# Piggyback-Board.net
KiCad netlist of a schematic drawn in EAGLE
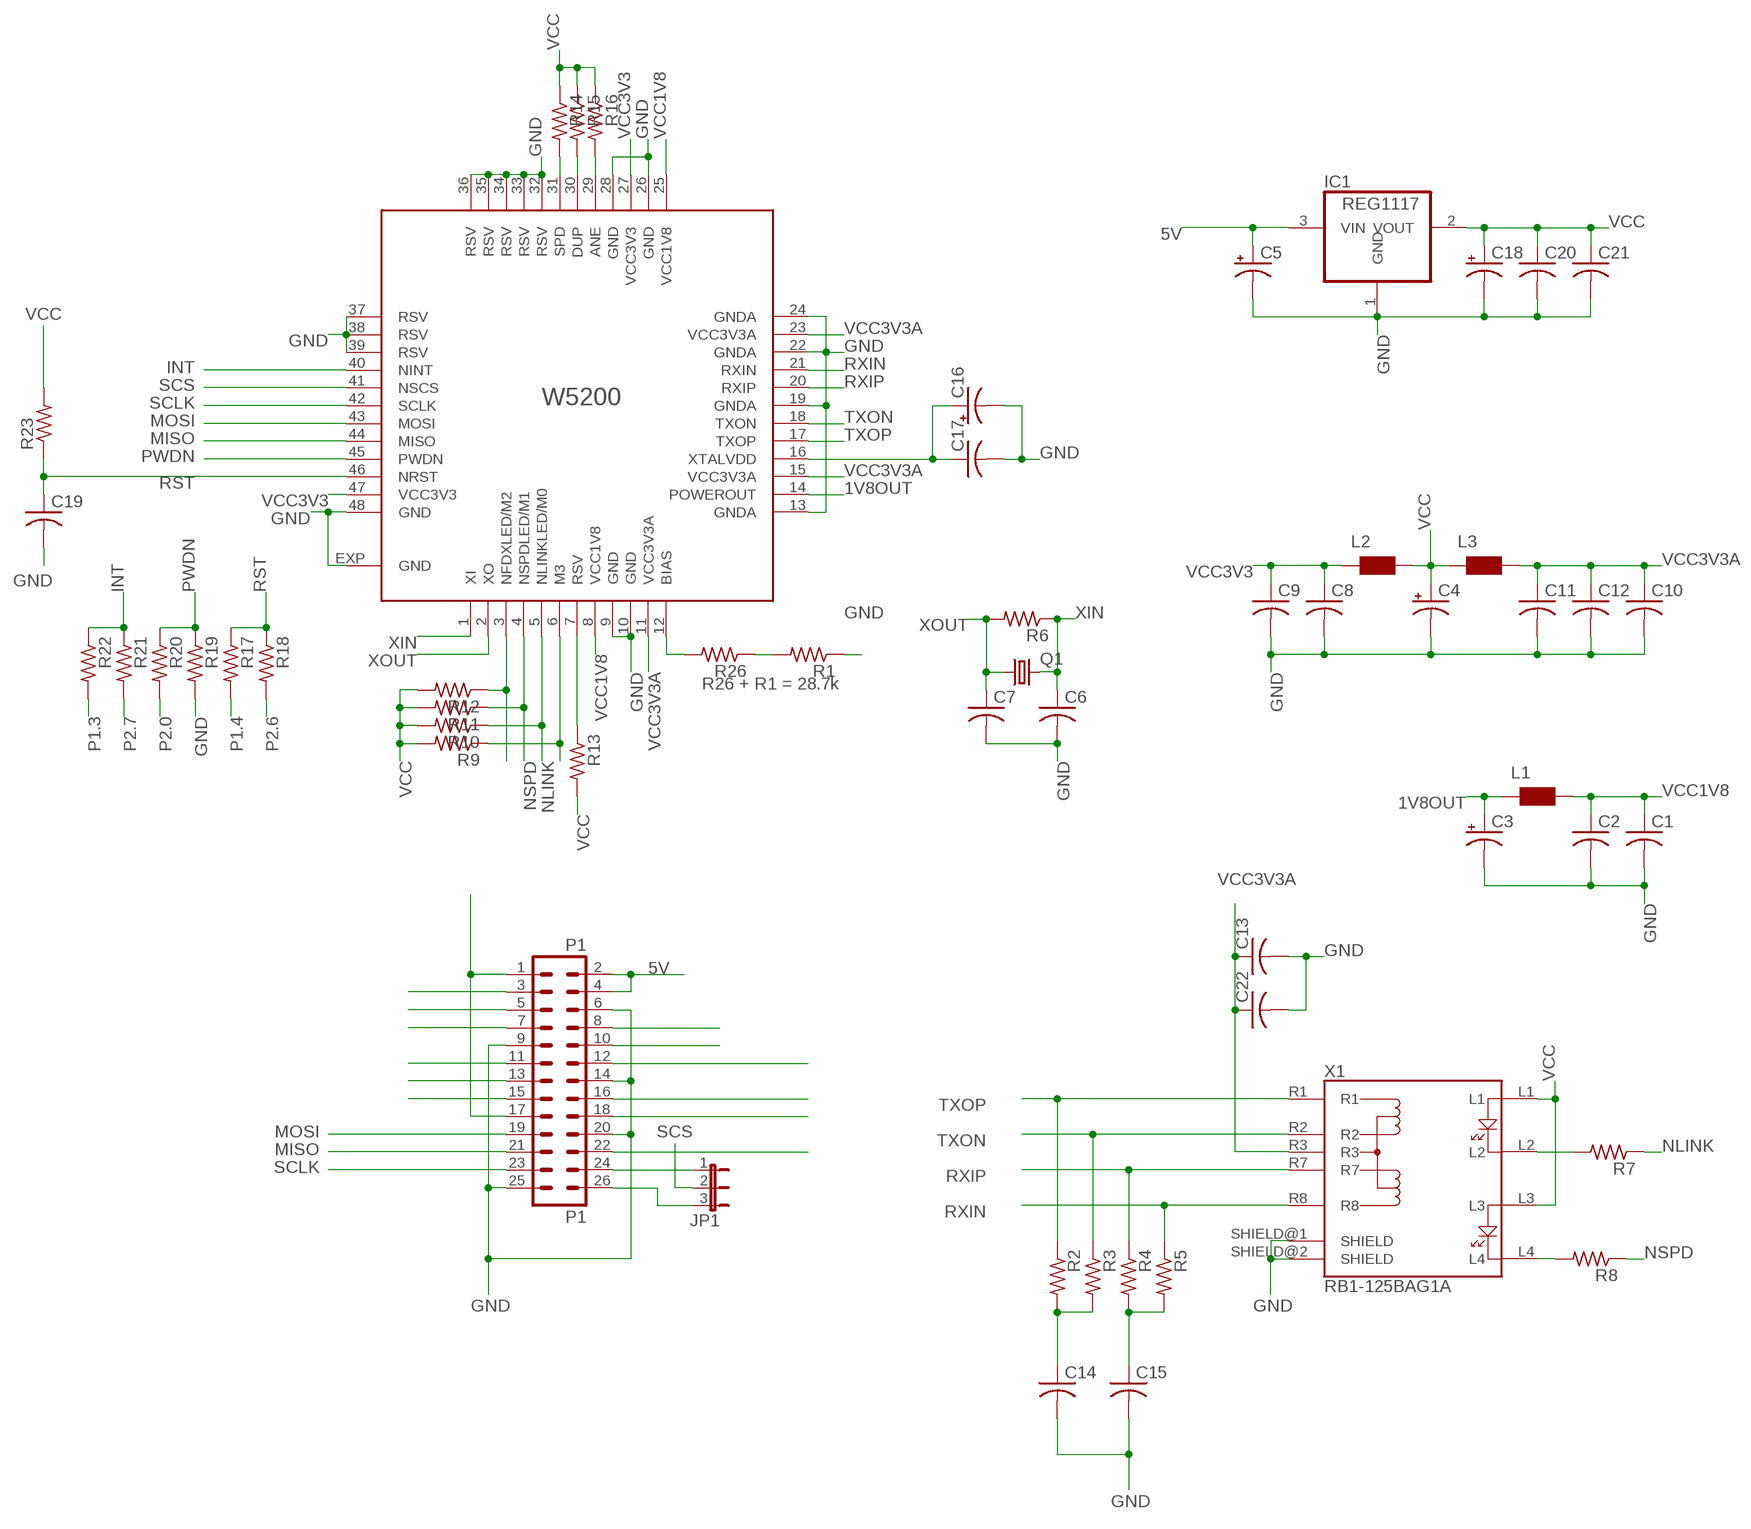
[diagram p0: schematic, sheet 1]

(export (version "E")
  (design (tool "Eeschema 10.0.6"))
  (components
    (comp (ref "C1")
      (value "C-USC0603")
      (footprint "eagle-import:C0603")
      (libsource (lib "eagle-import") (part "C-USC0603"))
    )
    (comp (ref "C2")
      (value "C-USC0603")
      (footprint "eagle-import:C0603")
      (libsource (lib "eagle-import") (part "C-USC0603"))
    )
    (comp (ref "C3")
      (value "CPOL-USA/3216-18R")
      (footprint "eagle-import:A_3216-18R")
      (libsource (lib "eagle-import") (part "CPOL-USA/3216-18R"))
    )
    (comp (ref "C4")
      (value "CPOL-USA/3216-18R")
      (footprint "eagle-import:A_3216-18R")
      (libsource (lib "eagle-import") (part "CPOL-USA/3216-18R"))
    )
    (comp (ref "C5")
      (value "CPOL-USB/3528-21R")
      (footprint "eagle-import:B_3528-21R")
      (libsource (lib "eagle-import") (part "CPOL-USB/3528-21R"))
    )
    (comp (ref "C6")
      (value "C-USC0603")
      (footprint "eagle-import:C0603")
      (libsource (lib "eagle-import") (part "C-USC0603"))
    )
    (comp (ref "C7")
      (value "C-USC0603")
      (footprint "eagle-import:C0603")
      (libsource (lib "eagle-import") (part "C-USC0603"))
    )
    (comp (ref "C8")
      (value "C-USC0603")
      (footprint "eagle-import:C0603")
      (libsource (lib "eagle-import") (part "C-USC0603"))
    )
    (comp (ref "C9")
      (value "C-USC0603")
      (footprint "eagle-import:C0603")
      (libsource (lib "eagle-import") (part "C-USC0603"))
    )
    (comp (ref "C10")
      (value "C-USC0603")
      (footprint "eagle-import:C0603")
      (libsource (lib "eagle-import") (part "C-USC0603"))
    )
    (comp (ref "C11")
      (value "C-USC0603")
      (footprint "eagle-import:C0603")
      (libsource (lib "eagle-import") (part "C-USC0603"))
    )
    (comp (ref "C12")
      (value "C-USC0603")
      (footprint "eagle-import:C0603")
      (libsource (lib "eagle-import") (part "C-USC0603"))
    )
    (comp (ref "C13")
      (value "C-USC0603")
      (footprint "eagle-import:C0603")
      (libsource (lib "eagle-import") (part "C-USC0603"))
    )
    (comp (ref "C14")
      (value "C-USC0603")
      (footprint "eagle-import:C0603")
      (libsource (lib "eagle-import") (part "C-USC0603"))
    )
    (comp (ref "C15")
      (value "C-USC0603")
      (footprint "eagle-import:C0603")
      (libsource (lib "eagle-import") (part "C-USC0603"))
    )
    (comp (ref "C16")
      (value "CPOL-USA/3216-18R")
      (footprint "eagle-import:A_3216-18R")
      (libsource (lib "eagle-import") (part "CPOL-USA/3216-18R"))
    )
    (comp (ref "C17")
      (value "C-USC0603")
      (footprint "eagle-import:C0603")
      (libsource (lib "eagle-import") (part "C-USC0603"))
    )
    (comp (ref "C18")
      (value "CPOL-USB/3528-21R")
      (footprint "eagle-import:B_3528-21R")
      (libsource (lib "eagle-import") (part "CPOL-USB/3528-21R"))
    )
    (comp (ref "C19")
      (value "C-USC0603")
      (footprint "eagle-import:C0603")
      (libsource (lib "eagle-import") (part "C-USC0603"))
    )
    (comp (ref "C20")
      (value "C-USC0603")
      (footprint "eagle-import:C0603")
      (libsource (lib "eagle-import") (part "C-USC0603"))
    )
    (comp (ref "C21")
      (value "C-USC0603")
      (footprint "eagle-import:C0603")
      (libsource (lib "eagle-import") (part "C-USC0603"))
    )
    (comp (ref "C22")
      (value "C-USC0603")
      (footprint "eagle-import:C0603")
      (libsource (lib "eagle-import") (part "C-USC0603"))
    )
    (comp (ref "IC1")
      (value "REG1117")
      (footprint "eagle-import:SOT223")
      (libsource (lib "eagle-import") (part "REG1117"))
    )
    (comp (ref "JP1")
      (value "JP2E")
      (footprint "eagle-import:JP2")
      (libsource (lib "eagle-import") (part "JP2E"))
    )
    (comp (ref "L1")
      (value "WE-CBF_0603")
      (footprint "eagle-import:0603")
      (libsource (lib "eagle-import") (part "WE-CBF_0603"))
    )
    (comp (ref "L2")
      (value "WE-CBF_0603")
      (footprint "eagle-import:0603")
      (libsource (lib "eagle-import") (part "WE-CBF_0603"))
    )
    (comp (ref "L3")
      (value "WE-CBF_0603")
      (footprint "eagle-import:0603")
      (libsource (lib "eagle-import") (part "WE-CBF_0603"))
    )
    (comp (ref "P1")
      (value "P1")
      (footprint "eagle-import:MA13-2")
      (libsource (lib "eagle-import") (part "MA13-2"))
    )
    (comp (ref "Q1")
      (value "CRYSTALSM49")
      (footprint "eagle-import:SM49")
      (libsource (lib "eagle-import") (part "CRYSTALSM49"))
    )
    (comp (ref "R1")
      (value "R-US_R0603")
      (footprint "eagle-import:R0603")
      (libsource (lib "eagle-import") (part "R-US_R0603"))
    )
    (comp (ref "R2")
      (value "R-US_R0603")
      (footprint "eagle-import:R0603")
      (libsource (lib "eagle-import") (part "R-US_R0603"))
    )
    (comp (ref "R3")
      (value "R-US_R0603")
      (footprint "eagle-import:R0603")
      (libsource (lib "eagle-import") (part "R-US_R0603"))
    )
    (comp (ref "R4")
      (value "R-US_R0603")
      (footprint "eagle-import:R0603")
      (libsource (lib "eagle-import") (part "R-US_R0603"))
    )
    (comp (ref "R5")
      (value "R-US_R0603")
      (footprint "eagle-import:R0603")
      (libsource (lib "eagle-import") (part "R-US_R0603"))
    )
    (comp (ref "R6")
      (value "R-US_R0603")
      (footprint "eagle-import:R0603")
      (libsource (lib "eagle-import") (part "R-US_R0603"))
    )
    (comp (ref "R7")
      (value "R-US_R0603")
      (footprint "eagle-import:R0603")
      (libsource (lib "eagle-import") (part "R-US_R0603"))
    )
    (comp (ref "R8")
      (value "R-US_R0603")
      (footprint "eagle-import:R0603")
      (libsource (lib "eagle-import") (part "R-US_R0603"))
    )
    (comp (ref "R9")
      (value "R-US_R0603")
      (footprint "eagle-import:R0603")
      (libsource (lib "eagle-import") (part "R-US_R0603"))
    )
    (comp (ref "R10")
      (value "R-US_R0603")
      (footprint "eagle-import:R0603")
      (libsource (lib "eagle-import") (part "R-US_R0603"))
    )
    (comp (ref "R11")
      (value "R-US_R0603")
      (footprint "eagle-import:R0603")
      (libsource (lib "eagle-import") (part "R-US_R0603"))
    )
    (comp (ref "R12")
      (value "R-US_R0603")
      (footprint "eagle-import:R0603")
      (libsource (lib "eagle-import") (part "R-US_R0603"))
    )
    (comp (ref "R13")
      (value "R-US_R0603")
      (footprint "eagle-import:R0603")
      (libsource (lib "eagle-import") (part "R-US_R0603"))
    )
    (comp (ref "R14")
      (value "R-US_R0603")
      (footprint "eagle-import:R0603")
      (libsource (lib "eagle-import") (part "R-US_R0603"))
    )
    (comp (ref "R15")
      (value "R-US_R0603")
      (footprint "eagle-import:R0603")
      (libsource (lib "eagle-import") (part "R-US_R0603"))
    )
    (comp (ref "R16")
      (value "R-US_R0603")
      (footprint "eagle-import:R0603")
      (libsource (lib "eagle-import") (part "R-US_R0603"))
    )
    (comp (ref "R17")
      (value "R-US_R0603")
      (footprint "eagle-import:R0603")
      (libsource (lib "eagle-import") (part "R-US_R0603"))
    )
    (comp (ref "R18")
      (value "R-US_R0603")
      (footprint "eagle-import:R0603")
      (libsource (lib "eagle-import") (part "R-US_R0603"))
    )
    (comp (ref "R19")
      (value "R-US_R0603")
      (footprint "eagle-import:R0603")
      (libsource (lib "eagle-import") (part "R-US_R0603"))
    )
    (comp (ref "R20")
      (value "R-US_R0603")
      (footprint "eagle-import:R0603")
      (libsource (lib "eagle-import") (part "R-US_R0603"))
    )
    (comp (ref "R21")
      (value "R-US_R0603")
      (footprint "eagle-import:R0603")
      (libsource (lib "eagle-import") (part "R-US_R0603"))
    )
    (comp (ref "R22")
      (value "R-US_R0603")
      (footprint "eagle-import:R0603")
      (libsource (lib "eagle-import") (part "R-US_R0603"))
    )
    (comp (ref "R23")
      (value "R-US_R0603")
      (footprint "eagle-import:R0603")
      (libsource (lib "eagle-import") (part "R-US_R0603"))
    )
    (comp (ref "R26")
      (value "R-US_R0603")
      (footprint "eagle-import:R0603")
      (libsource (lib "eagle-import") (part "R-US_R0603"))
    )
    (comp (ref "W5200")
      (value "W5200")
      (footprint "eagle-import:QFN48")
      (libsource (lib "eagle-import") (part "W5200"))
    )
    (comp (ref "X1")
      (value "RB1-125BAG1A")
      (footprint "eagle-import:RB1-125BAG1A")
      (libsource (lib "eagle-import") (part "RB1-125BAG1A"))
    )
  )
  (nets
    (net (code "1") (name "/1V8OUT") (class "Default")
      (node (ref "C3") (pin "+") (pinfunction "+_+") (pintype "passive"))
      (node (ref "L1") (pin "1") (pinfunction "1_1") (pintype "passive"))
      (node (ref "W5200") (pin "14") (pinfunction "POWEROUT_14") (pintype "bidirectional"))
    )
    (net (code "2") (name "/5V") (class "Default")
      (node (ref "C5") (pin "+") (pinfunction "+_+") (pintype "passive"))
      (node (ref "IC1") (pin "3") (pinfunction "VIN_3") (pintype "input"))
      (node (ref "P1") (pin "2") (pinfunction "2_2") (pintype "passive"))
      (node (ref "P1") (pin "4") (pinfunction "4_4") (pintype "passive"))
    )
    (net (code "3") (name "/GND") (class "Default")
      (node (ref "C1") (pin "2") (pinfunction "2_2") (pintype "passive"))
      (node (ref "C10") (pin "2") (pinfunction "2_2") (pintype "passive"))
      (node (ref "C11") (pin "2") (pinfunction "2_2") (pintype "passive"))
      (node (ref "C12") (pin "2") (pinfunction "2_2") (pintype "passive"))
      (node (ref "C13") (pin "2") (pinfunction "2_2") (pintype "passive"))
      (node (ref "C14") (pin "2") (pinfunction "2_2") (pintype "passive"))
      (node (ref "C15") (pin "2") (pinfunction "2_2") (pintype "passive"))
      (node (ref "C16") (pin "-") (pinfunction "-_-") (pintype "passive"))
      (node (ref "C17") (pin "2") (pinfunction "2_2") (pintype "passive"))
      (node (ref "C18") (pin "-") (pinfunction "-_-") (pintype "passive"))
      (node (ref "C19") (pin "2") (pinfunction "2_2") (pintype "passive"))
      (node (ref "C2") (pin "2") (pinfunction "2_2") (pintype "passive"))
      (node (ref "C20") (pin "2") (pinfunction "2_2") (pintype "passive"))
      (node (ref "C21") (pin "2") (pinfunction "2_2") (pintype "passive"))
      (node (ref "C22") (pin "2") (pinfunction "2_2") (pintype "passive"))
      (node (ref "C3") (pin "-") (pinfunction "-_-") (pintype "passive"))
      (node (ref "C4") (pin "-") (pinfunction "-_-") (pintype "passive"))
      (node (ref "C5") (pin "-") (pinfunction "-_-") (pintype "passive"))
      (node (ref "C6") (pin "2") (pinfunction "2_2") (pintype "passive"))
      (node (ref "C7") (pin "2") (pinfunction "2_2") (pintype "passive"))
      (node (ref "C8") (pin "2") (pinfunction "2_2") (pintype "passive"))
      (node (ref "C9") (pin "2") (pinfunction "2_2") (pintype "passive"))
      (node (ref "IC1") (pin "1") (pinfunction "GND_1") (pintype "power_in"))
      (node (ref "P1") (pin "14") (pinfunction "14_14") (pintype "passive"))
      (node (ref "P1") (pin "20") (pinfunction "20_20") (pintype "passive"))
      (node (ref "P1") (pin "25") (pinfunction "25_25") (pintype "passive"))
      (node (ref "P1") (pin "6") (pinfunction "6_6") (pintype "passive"))
      (node (ref "P1") (pin "9") (pinfunction "9_9") (pintype "passive"))
      (node (ref "R1") (pin "1") (pinfunction "1_1") (pintype "passive"))
      (node (ref "R19") (pin "2") (pinfunction "2_2") (pintype "passive"))
      (node (ref "W5200") (pin "10") (pinfunction "GND_10") (pintype "bidirectional"))
      (node (ref "W5200") (pin "13") (pinfunction "GNDA_13") (pintype "bidirectional"))
      (node (ref "W5200") (pin "19") (pinfunction "GNDA_19") (pintype "bidirectional"))
      (node (ref "W5200") (pin "22") (pinfunction "GNDA_22") (pintype "bidirectional"))
      (node (ref "W5200") (pin "24") (pinfunction "GNDA_24") (pintype "bidirectional"))
      (node (ref "W5200") (pin "26") (pinfunction "GND_26") (pintype "bidirectional"))
      (node (ref "W5200") (pin "28") (pinfunction "GND_28") (pintype "bidirectional"))
      (node (ref "W5200") (pin "32") (pinfunction "RSV_32") (pintype "bidirectional"))
      (node (ref "W5200") (pin "33") (pinfunction "RSV_33") (pintype "bidirectional"))
      (node (ref "W5200") (pin "34") (pinfunction "RSV_34") (pintype "bidirectional"))
      (node (ref "W5200") (pin "35") (pinfunction "RSV_35") (pintype "bidirectional"))
      (node (ref "W5200") (pin "36") (pinfunction "RSV_36") (pintype "bidirectional"))
      (node (ref "W5200") (pin "37") (pinfunction "RSV_37") (pintype "bidirectional"))
      (node (ref "W5200") (pin "38") (pinfunction "RSV_38") (pintype "bidirectional"))
      (node (ref "W5200") (pin "39") (pinfunction "RSV_39") (pintype "bidirectional"))
      (node (ref "W5200") (pin "48") (pinfunction "GND_48") (pintype "bidirectional"))
      (node (ref "W5200") (pin "9") (pinfunction "GND_9") (pintype "bidirectional"))
      (node (ref "W5200") (pin "EXP") (pinfunction "GND_EXP") (pintype "bidirectional"))
      (node (ref "X1") (pin "SHIELD@1") (pinfunction "SHIELD_SHIELD@1") (pintype "bidirectional"))
      (node (ref "X1") (pin "SHIELD@2") (pinfunction "SHIELD_SHIELD@2") (pintype "bidirectional"))
    )
    (net (code "4") (name "/INT") (class "Default")
      (node (ref "R21") (pin "1") (pinfunction "1_1") (pintype "passive"))
      (node (ref "R22") (pin "1") (pinfunction "1_1") (pintype "passive"))
      (node (ref "W5200") (pin "40") (pinfunction "NINT_40") (pintype "bidirectional"))
    )
    (net (code "5") (name "/MISO") (class "Default")
      (node (ref "P1") (pin "21") (pinfunction "21_21") (pintype "passive"))
      (node (ref "W5200") (pin "44") (pinfunction "MISO_44") (pintype "bidirectional"))
    )
    (net (code "6") (name "/MOSI") (class "Default")
      (node (ref "P1") (pin "19") (pinfunction "19_19") (pintype "passive"))
      (node (ref "W5200") (pin "43") (pinfunction "MOSI_43") (pintype "bidirectional"))
    )
    (net (code "7") (name "/NLINK") (class "Default")
      (node (ref "R10") (pin "1") (pinfunction "1_1") (pintype "passive"))
      (node (ref "R7") (pin "1") (pinfunction "1_1") (pintype "passive"))
      (node (ref "W5200") (pin "5") (pinfunction "NLINKLED/M0_5") (pintype "bidirectional"))
    )
    (net (code "8") (name "/NSPD") (class "Default")
      (node (ref "R11") (pin "1") (pinfunction "1_1") (pintype "passive"))
      (node (ref "R8") (pin "1") (pinfunction "1_1") (pintype "passive"))
      (node (ref "W5200") (pin "4") (pinfunction "NSPDLED/M1_4") (pintype "bidirectional"))
    )
    (net (code "9") (name "/P1.3") (class "Default")
      (node (ref "R22") (pin "2") (pinfunction "2_2") (pintype "passive"))
    )
    (net (code "10") (name "/P1.4") (class "Default")
      (node (ref "R17") (pin "2") (pinfunction "2_2") (pintype "passive"))
    )
    (net (code "11") (name "/P2.0") (class "Default")
      (node (ref "R20") (pin "2") (pinfunction "2_2") (pintype "passive"))
    )
    (net (code "12") (name "/P2.6") (class "Default")
      (node (ref "R18") (pin "2") (pinfunction "2_2") (pintype "passive"))
    )
    (net (code "13") (name "/P2.7") (class "Default")
      (node (ref "R21") (pin "2") (pinfunction "2_2") (pintype "passive"))
    )
    (net (code "14") (name "/PWDN") (class "Default")
      (node (ref "R19") (pin "1") (pinfunction "1_1") (pintype "passive"))
      (node (ref "R20") (pin "1") (pinfunction "1_1") (pintype "passive"))
      (node (ref "W5200") (pin "45") (pinfunction "PWDN_45") (pintype "bidirectional"))
    )
    (net (code "15") (name "/RST") (class "Default")
      (node (ref "C19") (pin "1") (pinfunction "1_1") (pintype "passive"))
      (node (ref "R17") (pin "1") (pinfunction "1_1") (pintype "passive"))
      (node (ref "R18") (pin "1") (pinfunction "1_1") (pintype "passive"))
      (node (ref "R23") (pin "1") (pinfunction "1_1") (pintype "passive"))
      (node (ref "W5200") (pin "46") (pinfunction "NRST_46") (pintype "bidirectional"))
    )
    (net (code "16") (name "/RXIN") (class "Default")
      (node (ref "R5") (pin "1") (pinfunction "1_1") (pintype "passive"))
      (node (ref "W5200") (pin "21") (pinfunction "RXIN_21") (pintype "bidirectional"))
      (node (ref "X1") (pin "R8") (pinfunction "R8_R8") (pintype "bidirectional"))
    )
    (net (code "17") (name "/RXIP") (class "Default")
      (node (ref "R4") (pin "1") (pinfunction "1_1") (pintype "passive"))
      (node (ref "W5200") (pin "20") (pinfunction "RXIP_20") (pintype "bidirectional"))
      (node (ref "X1") (pin "R7") (pinfunction "R7_R7") (pintype "bidirectional"))
    )
    (net (code "18") (name "/SCLK") (class "Default")
      (node (ref "P1") (pin "23") (pinfunction "23_23") (pintype "passive"))
      (node (ref "W5200") (pin "42") (pinfunction "SCLK_42") (pintype "bidirectional"))
    )
    (net (code "19") (name "/SCS") (class "Default")
      (node (ref "JP1") (pin "2") (pinfunction "2_2") (pintype "passive"))
      (node (ref "W5200") (pin "41") (pinfunction "NSCS_41") (pintype "bidirectional"))
    )
    (net (code "20") (name "/TXON") (class "Default")
      (node (ref "R3") (pin "1") (pinfunction "1_1") (pintype "passive"))
      (node (ref "W5200") (pin "18") (pinfunction "TXON_18") (pintype "bidirectional"))
      (node (ref "X1") (pin "R2") (pinfunction "R2_R2") (pintype "bidirectional"))
    )
    (net (code "21") (name "/TXOP") (class "Default")
      (node (ref "R2") (pin "1") (pinfunction "1_1") (pintype "passive"))
      (node (ref "W5200") (pin "17") (pinfunction "TXOP_17") (pintype "bidirectional"))
      (node (ref "X1") (pin "R1") (pinfunction "R1_R1") (pintype "bidirectional"))
    )
    (net (code "22") (name "/VCC") (class "Default")
      (node (ref "C18") (pin "+") (pinfunction "+_+") (pintype "passive"))
      (node (ref "C20") (pin "1") (pinfunction "1_1") (pintype "passive"))
      (node (ref "C21") (pin "1") (pinfunction "1_1") (pintype "passive"))
      (node (ref "C4") (pin "+") (pinfunction "+_+") (pintype "passive"))
      (node (ref "IC1") (pin "2") (pinfunction "VOUT_2") (pintype "output"))
      (node (ref "L2") (pin "2") (pinfunction "2_2") (pintype "passive"))
      (node (ref "L3") (pin "1") (pinfunction "1_1") (pintype "passive"))
      (node (ref "R10") (pin "2") (pinfunction "2_2") (pintype "passive"))
      (node (ref "R11") (pin "2") (pinfunction "2_2") (pintype "passive"))
      (node (ref "R12") (pin "2") (pinfunction "2_2") (pintype "passive"))
      (node (ref "R13") (pin "2") (pinfunction "2_2") (pintype "passive"))
      (node (ref "R14") (pin "1") (pinfunction "1_1") (pintype "passive"))
      (node (ref "R15") (pin "1") (pinfunction "1_1") (pintype "passive"))
      (node (ref "R16") (pin "1") (pinfunction "1_1") (pintype "passive"))
      (node (ref "R23") (pin "2") (pinfunction "2_2") (pintype "passive"))
      (node (ref "R9") (pin "2") (pinfunction "2_2") (pintype "passive"))
      (node (ref "X1") (pin "L1") (pinfunction "L1_L1") (pintype "bidirectional"))
      (node (ref "X1") (pin "L3") (pinfunction "L3_L3") (pintype "bidirectional"))
    )
    (net (code "23") (name "/VCC1V8") (class "Default")
      (node (ref "C1") (pin "1") (pinfunction "1_1") (pintype "passive"))
      (node (ref "C2") (pin "1") (pinfunction "1_1") (pintype "passive"))
      (node (ref "L1") (pin "2") (pinfunction "2_2") (pintype "passive"))
      (node (ref "W5200") (pin "25") (pinfunction "VCC1V8_25") (pintype "bidirectional"))
      (node (ref "W5200") (pin "8") (pinfunction "VCC1V8_8") (pintype "bidirectional"))
    )
    (net (code "24") (name "/VCC3V3") (class "Default")
      (node (ref "C8") (pin "1") (pinfunction "1_1") (pintype "passive"))
      (node (ref "C9") (pin "1") (pinfunction "1_1") (pintype "passive"))
      (node (ref "L2") (pin "1") (pinfunction "1_1") (pintype "passive"))
      (node (ref "W5200") (pin "27") (pinfunction "VCC3V3_27") (pintype "bidirectional"))
      (node (ref "W5200") (pin "47") (pinfunction "VCC3V3_47") (pintype "bidirectional"))
    )
    (net (code "25") (name "/VCC3V3A") (class "Default")
      (node (ref "C10") (pin "1") (pinfunction "1_1") (pintype "passive"))
      (node (ref "C11") (pin "1") (pinfunction "1_1") (pintype "passive"))
      (node (ref "C12") (pin "1") (pinfunction "1_1") (pintype "passive"))
      (node (ref "C13") (pin "1") (pinfunction "1_1") (pintype "passive"))
      (node (ref "C22") (pin "1") (pinfunction "1_1") (pintype "passive"))
      (node (ref "L3") (pin "2") (pinfunction "2_2") (pintype "passive"))
      (node (ref "W5200") (pin "11") (pinfunction "VCC3V3A_11") (pintype "bidirectional"))
      (node (ref "W5200") (pin "15") (pinfunction "VCC3V3A_15") (pintype "bidirectional"))
      (node (ref "W5200") (pin "23") (pinfunction "VCC3V3A_23") (pintype "bidirectional"))
      (node (ref "X1") (pin "R3") (pinfunction "R3_R3") (pintype "bidirectional"))
    )
    (net (code "26") (name "/XIN") (class "Default")
      (node (ref "C6") (pin "1") (pinfunction "1_1") (pintype "passive"))
      (node (ref "Q1") (pin "2") (pinfunction "2_2") (pintype "passive"))
      (node (ref "R6") (pin "1") (pinfunction "1_1") (pintype "passive"))
      (node (ref "W5200") (pin "1") (pinfunction "XI_1") (pintype "bidirectional"))
    )
    (net (code "27") (name "/XOUT") (class "Default")
      (node (ref "C7") (pin "1") (pinfunction "1_1") (pintype "passive"))
      (node (ref "Q1") (pin "1") (pinfunction "1_1") (pintype "passive"))
      (node (ref "R6") (pin "2") (pinfunction "2_2") (pintype "passive"))
      (node (ref "W5200") (pin "2") (pinfunction "XO_2") (pintype "bidirectional"))
    )
    (net (code "28") (name "Net-(C14-Pad1)") (class "Default")
      (node (ref "C14") (pin "1") (pinfunction "1_1") (pintype "passive"))
      (node (ref "R2") (pin "2") (pinfunction "2_2") (pintype "passive"))
      (node (ref "R3") (pin "2") (pinfunction "2_2") (pintype "passive"))
    )
    (net (code "29") (name "Net-(C15-Pad1)") (class "Default")
      (node (ref "C15") (pin "1") (pinfunction "1_1") (pintype "passive"))
      (node (ref "R4") (pin "2") (pinfunction "2_2") (pintype "passive"))
      (node (ref "R5") (pin "2") (pinfunction "2_2") (pintype "passive"))
    )
    (net (code "30") (name "Net-(JP1-Pad1)") (class "Default")
      (node (ref "JP1") (pin "1") (pinfunction "1_1") (pintype "passive"))
      (node (ref "P1") (pin "24") (pinfunction "24_24") (pintype "passive"))
    )
    (net (code "31") (name "Net-(JP1-Pad3)") (class "Default")
      (node (ref "JP1") (pin "3") (pinfunction "3_3") (pintype "passive"))
      (node (ref "P1") (pin "26") (pinfunction "26_26") (pintype "passive"))
    )
    (net (code "32") (name "Net-(P1-Pad1)") (class "Default")
      (node (ref "P1") (pin "1") (pinfunction "1_1") (pintype "passive"))
      (node (ref "P1") (pin "17") (pinfunction "17_17") (pintype "passive"))
    )
    (net (code "33") (name "Net-(R1-Pad2)") (class "Default")
      (node (ref "R1") (pin "2") (pinfunction "2_2") (pintype "passive"))
      (node (ref "R26") (pin "1") (pinfunction "1_1") (pintype "passive"))
    )
    (net (code "34") (name "Net-(R7-Pad2)") (class "Default")
      (node (ref "R7") (pin "2") (pinfunction "2_2") (pintype "passive"))
      (node (ref "X1") (pin "L2") (pinfunction "L2_L2") (pintype "bidirectional"))
    )
    (net (code "35") (name "Net-(R8-Pad2)") (class "Default")
      (node (ref "R8") (pin "2") (pinfunction "2_2") (pintype "passive"))
      (node (ref "X1") (pin "L4") (pinfunction "L4_L4") (pintype "bidirectional"))
    )
    (net (code "36") (name "Net-(R13-Pad1)") (class "Default")
      (node (ref "R13") (pin "1") (pinfunction "1_1") (pintype "passive"))
      (node (ref "W5200") (pin "7") (pinfunction "RSV_7") (pintype "bidirectional"))
    )
    (net (code "37") (name "Net-(W5200-ANE)") (class "Default")
      (node (ref "R16") (pin "2") (pinfunction "2_2") (pintype "passive"))
      (node (ref "W5200") (pin "29") (pinfunction "ANE_29") (pintype "bidirectional"))
    )
    (net (code "38") (name "Net-(W5200-BIAS)") (class "Default")
      (node (ref "R26") (pin "2") (pinfunction "2_2") (pintype "passive"))
      (node (ref "W5200") (pin "12") (pinfunction "BIAS_12") (pintype "bidirectional"))
    )
    (net (code "39") (name "Net-(W5200-DUP)") (class "Default")
      (node (ref "R15") (pin "2") (pinfunction "2_2") (pintype "passive"))
      (node (ref "W5200") (pin "30") (pinfunction "DUP_30") (pintype "bidirectional"))
    )
    (net (code "40") (name "Net-(W5200-M3)") (class "Default")
      (node (ref "R9") (pin "1") (pinfunction "1_1") (pintype "passive"))
      (node (ref "W5200") (pin "6") (pinfunction "M3_6") (pintype "bidirectional"))
    )
    (net (code "41") (name "Net-(W5200-NFDXLED{slash}M2)") (class "Default")
      (node (ref "R12") (pin "1") (pinfunction "1_1") (pintype "passive"))
      (node (ref "W5200") (pin "3") (pinfunction "NFDXLED/M2_3") (pintype "bidirectional"))
    )
    (net (code "42") (name "Net-(W5200-SPD)") (class "Default")
      (node (ref "R14") (pin "2") (pinfunction "2_2") (pintype "passive"))
      (node (ref "W5200") (pin "31") (pinfunction "SPD_31") (pintype "bidirectional"))
    )
    (net (code "43") (name "Net-(W5200-XTALVDD)") (class "Default")
      (node (ref "C16") (pin "+") (pinfunction "+_+") (pintype "passive"))
      (node (ref "C17") (pin "1") (pinfunction "1_1") (pintype "passive"))
      (node (ref "W5200") (pin "16") (pinfunction "XTALVDD_16") (pintype "bidirectional"))
    )
    (net (code "44") (name "unconnected-(P1-Pad3)") (class "Default")
      (node (ref "P1") (pin "3") (pinfunction "3_3") (pintype "passive"))
    )
    (net (code "45") (name "unconnected-(P1-Pad5)") (class "Default")
      (node (ref "P1") (pin "5") (pinfunction "5_5") (pintype "passive"))
    )
    (net (code "46") (name "unconnected-(P1-Pad7)") (class "Default")
      (node (ref "P1") (pin "7") (pinfunction "7_7") (pintype "passive"))
    )
    (net (code "47") (name "unconnected-(P1-Pad8)") (class "Default")
      (node (ref "P1") (pin "8") (pinfunction "8_8") (pintype "passive"))
    )
    (net (code "48") (name "unconnected-(P1-Pad10)") (class "Default")
      (node (ref "P1") (pin "10") (pinfunction "10_10") (pintype "passive"))
    )
    (net (code "49") (name "unconnected-(P1-Pad11)") (class "Default")
      (node (ref "P1") (pin "11") (pinfunction "11_11") (pintype "passive"))
    )
    (net (code "50") (name "unconnected-(P1-Pad12)") (class "Default")
      (node (ref "P1") (pin "12") (pinfunction "12_12") (pintype "passive"))
    )
    (net (code "51") (name "unconnected-(P1-Pad13)") (class "Default")
      (node (ref "P1") (pin "13") (pinfunction "13_13") (pintype "passive"))
    )
    (net (code "52") (name "unconnected-(P1-Pad15)") (class "Default")
      (node (ref "P1") (pin "15") (pinfunction "15_15") (pintype "passive"))
    )
    (net (code "53") (name "unconnected-(P1-Pad16)") (class "Default")
      (node (ref "P1") (pin "16") (pinfunction "16_16") (pintype "passive"))
    )
    (net (code "54") (name "unconnected-(P1-Pad18)") (class "Default")
      (node (ref "P1") (pin "18") (pinfunction "18_18") (pintype "passive"))
    )
    (net (code "55") (name "unconnected-(P1-Pad22)") (class "Default")
      (node (ref "P1") (pin "22") (pinfunction "22_22") (pintype "passive"))
    )
  )
)
